# Power_Management.net
KiCad netlist of a schematic drawn in Altium Designer
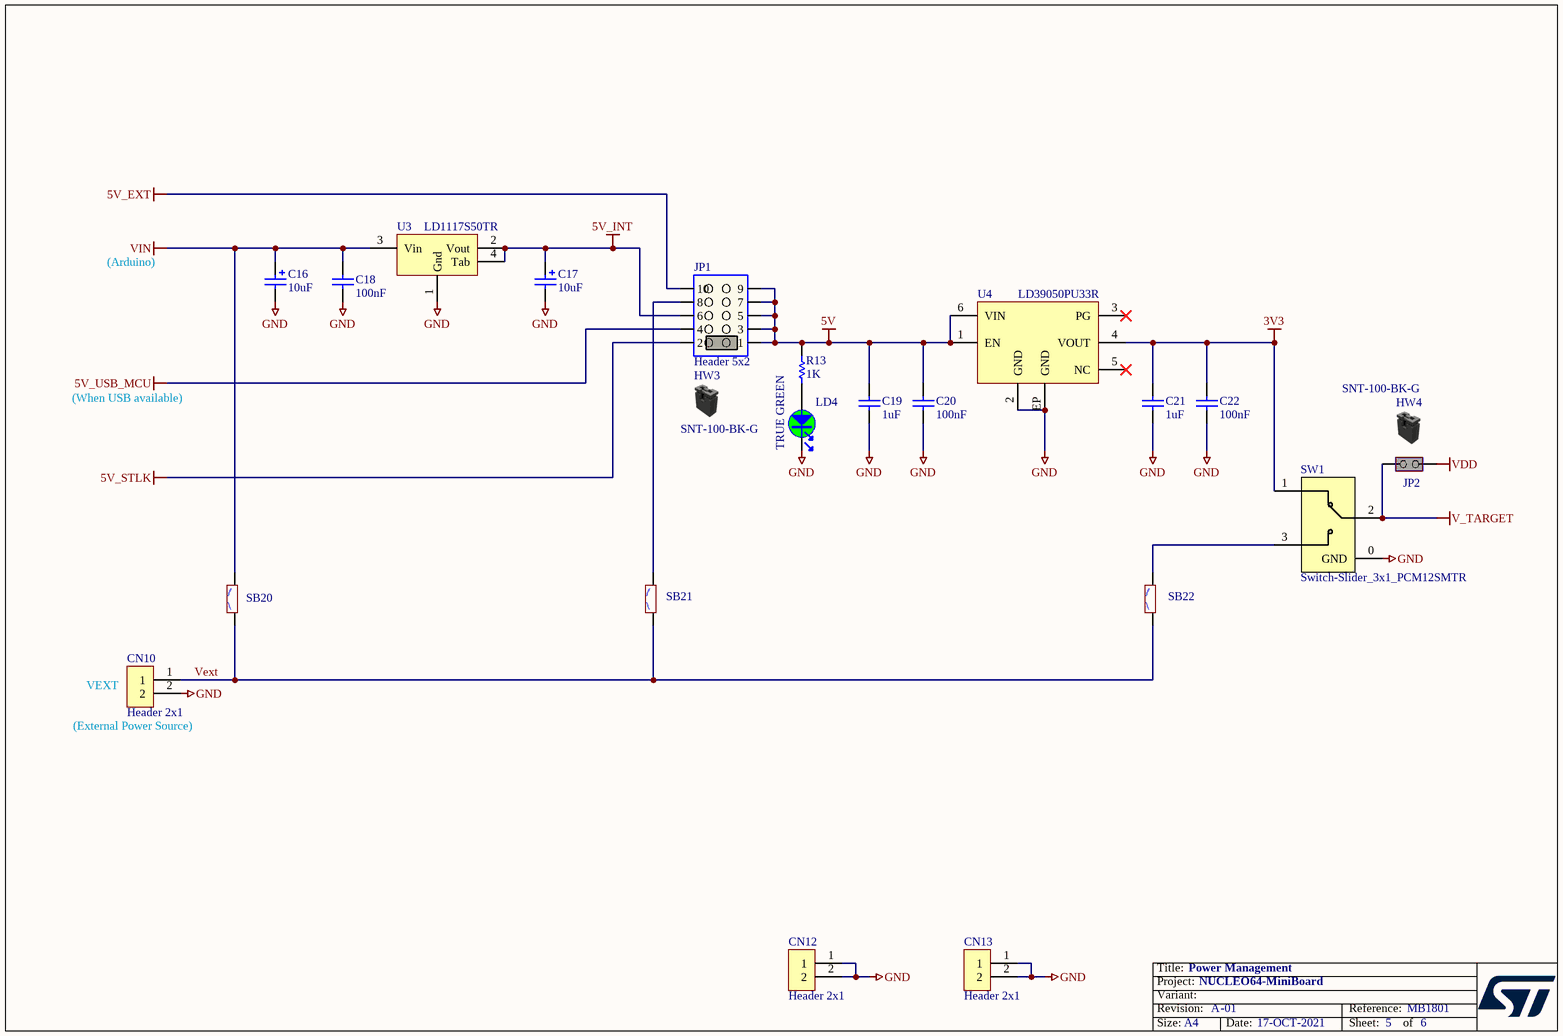
[diagram p0: Power_Management.SchDoc]

(export (version "E")
  (design (tool "Eeschema 10.0.6"))
  (components
    (comp (ref "C16")
      (value "10uF")
      (footprint "CPOL_TAJ-B_1210_H210")
      (description "Capacitor, Tantalum, 10uF, 25V, 2R5, +/-10%, Type_B (3528 metric), T=1.9mm")
      (fields
        (field (name "INTERNAL_PART_NUMBER") "MCD-00324")
        (field (name "MANUFACTURER_PART_NUMBER") "TAJB106K025RNJ")
      )
      (libsource (lib "MCD_PARTS_database") (part "Cap_POL_TANA"))
    )
    (comp (ref "C17")
      (value "10uF")
      (footprint "CPOL_TAJ-B_1210_H210")
      (description "Capacitor, Tantalum, 10uF, 25V, 2R5, +/-10%, Type_B (3528 metric), T=1.9mm")
      (fields
        (field (name "INTERNAL_PART_NUMBER") "MCD-00324")
        (field (name "MANUFACTURER_PART_NUMBER") "TAJB106K025RNJ")
      )
      (libsource (lib "MCD_PARTS_database") (part "Cap_POL_TANA"))
    )
    (comp (ref "C18")
      (value "100nF")
      (footprint "C0402")
      (description "Capacitor, MLCC, 100nF, 25V, X7R, +/-10%, 0402, T=0.5mm")
      (fields (field (name "INTERNAL_PART_NUMBER") "MCD-02355") (field (name "MANUFACTURER") "WALSIN"))
      (libsource (lib "MCD_PARTS_database") (part "Capacitor"))
    )
    (comp (ref "C19")
      (value "1uF")
      (footprint "C0805_H0P85")
      (description "Capacitor, MLCC, 1uF, 16V, X5R, +/-10%, 0805, T=0.85mm")
      (fields
        (field (name "INTERNAL_PART_NUMBER") "MCD-01550")
        (field (name "MANUFACTURER_PART_NUMBER") "CC0805KRX5R7BB105")
      )
      (libsource (lib "MCD_PARTS_database") (part "Capacitor"))
    )
    (comp (ref "C20")
      (value "100nF")
      (footprint "C0402")
      (description "Capacitor, MLCC, 100nF, 25V, X7R, +/-10%, 0402, T=0.5mm")
      (fields (field (name "INTERNAL_PART_NUMBER") "MCD-02355") (field (name "MANUFACTURER") "WALSIN"))
      (libsource (lib "MCD_PARTS_database") (part "Capacitor"))
    )
    (comp (ref "C21")
      (value "1uF")
      (footprint "C0805_H0P85")
      (description "Capacitor, MLCC, 1uF, 16V, X5R, +/-10%, 0805, T=0.85mm")
      (fields
        (field (name "INTERNAL_PART_NUMBER") "MCD-01550")
        (field (name "MANUFACTURER_PART_NUMBER") "CC0805KRX5R7BB105")
      )
      (libsource (lib "MCD_PARTS_database") (part "Capacitor"))
    )
    (comp (ref "C22")
      (value "100nF")
      (footprint "C0402")
      (description "Capacitor, MLCC, 100nF, 25V, X7R, +/-10%, 0402, T=0.5mm")
      (fields (field (name "INTERNAL_PART_NUMBER") "MCD-02355") (field (name "MANUFACTURER") "WALSIN"))
      (libsource (lib "MCD_PARTS_database") (part "Capacitor"))
    )
    (comp (ref "CN10")
      (value "Header 2x1")
      (footprint "CON_SAMTEC_TSW-102-07-G-S")
      (description "Header, 2x1, 2.54mm, VR, TH, T=5.84mm/2.54mm")
      (fields (field (name "INTERNAL_PART_NUMBER") "MCD-00032") (field (name "MANUFACTURER") "SAMTEC"))
      (libsource (lib "MCD_PARTS_database") (part "Header 2x1"))
    )
    (comp (ref "CN12")
      (value "Header 2x1")
      (footprint "CON_SAMTEC_TSW-102-07-G-S")
      (description "Header, 2x1, 2.54mm, VR, TH, T=5.84mm/2.54mm")
      (fields (field (name "INTERNAL_PART_NUMBER") "MCD-00032") (field (name "MANUFACTURER") "SAMTEC"))
      (libsource (lib "MCD_PARTS_database") (part "Header 2x1"))
    )
    (comp (ref "CN13")
      (value "Header 2x1")
      (footprint "CON_SAMTEC_TSW-102-07-G-S")
      (description "Header, 2x1, 2.54mm, VR, TH, T=5.84mm/2.54mm")
      (fields (field (name "INTERNAL_PART_NUMBER") "MCD-00032") (field (name "MANUFACTURER") "SAMTEC"))
      (libsource (lib "MCD_PARTS_database") (part "Header 2x1"))
    )
    (comp (ref "HW3")
      (value "SNT-100-BK-G")
      (description "SHUNT 2.54mm BLACK")
      (fields (field (name "INTERNAL_PART_NUMBER") "MCD-00043") (field (name "MANUFACTURER") "SAMTEC"))
      (libsource (lib "MCD_PARTS_database") (part "Shunt Black 2.54mm"))
    )
    (comp (ref "HW4")
      (value "SNT-100-BK-G")
      (description "SHUNT 2.54mm BLACK")
      (fields (field (name "INTERNAL_PART_NUMBER") "MCD-00043") (field (name "MANUFACTURER") "SAMTEC"))
      (libsource (lib "MCD_PARTS_database") (part "Shunt Black 2.54mm"))
    )
    (comp (ref "JP1")
      (value "Header 5x2")
      (footprint "CON_SAMTEC_TSM-105-01-L-DV")
      (description "Header, 5x2, 2.54mm, VR, SMD, T=5.84mm")
      (fields (field (name "INTERNAL_PART_NUMBER") "MCD-01230") (field (name "BMS_PART_NUMBER") "9183642"))
      (libsource (lib "MCD_PARTS_database") (part "Jumper_Header 5x2 Fitted 1-2"))
    )
    (comp (ref "JP2")
      (value "Jumper_Header 2x1 Fitted")
      (footprint "CON_SAMTEC_TSW-102-07-G-S")
      (description "Header, 2x1, 2.54mm, VR, TH, T=5.84mm/2.54mm")
      (fields
        (field (name "INTERNAL_PART_NUMBER") "MCD-01904")
        (field (name "MANUFACTURER_PART_NUMBER") "TSW-102-07-G-S")
      )
      (libsource (lib "MCD_PARTS_database") (part "Jumper_Header 2x1 Fitted"))
    )
    (comp (ref "LD4")
      (value "TRUE GREEN")
      (footprint "LED_0603_VISHAY_VLMTG1300-GS08_GREEN_1A2K_H0P8")
      (description "LED Green, 0603 SMD, Fw Voltage = 2.8V - 3.6V")
      (fields
        (field (name "INTERNAL_PART_NUMBER") "MCD-00589")
        (field (name "MANUFACTURER_PART_NUMBER") "VLMTG1300-GS08")
      )
      (libsource (lib "MCD_PARTS_database") (part "LED_green"))
    )
    (comp (ref "R13")
      (value "1K")
      (footprint "R0402")
      (description "Resistor, 1K, 0402, +/-1%,1/16W")
      (fields
        (field (name "INTERNAL_PART_NUMBER") "MCD-00061")
        (field (name "MANUFACTURER_PART_NUMBER") "RC0402FR-071KL")
      )
      (libsource (lib "MCD_PARTS_database") (part "Resistor"))
    )
    (comp (ref "SB20")
      (value "SB_OFF")
      (footprint "SOLDER-BRIDGE_R0402-0R")
      (description "Solder Bridge 0402 OFF")
      (fields (field (name "INTERNAL_PART_NUMBER") "MCD-02162") (field (name "MANUFACTURER") "YAGEO"))
      (libsource (lib "MCD_PARTS_database") (part "SB_OFF"))
    )
    (comp (ref "SB21")
      (value "SB_OFF")
      (footprint "SOLDER-BRIDGE_R0402-0R")
      (description "Solder Bridge 0402 OFF")
      (fields (field (name "INTERNAL_PART_NUMBER") "MCD-02162") (field (name "MANUFACTURER") "YAGEO"))
      (libsource (lib "MCD_PARTS_database") (part "SB_OFF"))
    )
    (comp (ref "SB22")
      (value "SB_OFF")
      (footprint "SOLDER-BRIDGE_R0402-0R")
      (description "Solder Bridge 0402 OFF")
      (fields (field (name "INTERNAL_PART_NUMBER") "MCD-02162") (field (name "MANUFACTURER") "YAGEO"))
      (libsource (lib "MCD_PARTS_database") (part "SB_OFF"))
    )
    (comp (ref "SW1")
      (value "Switch-Slider_3x1_PCM12SMTR")
      (footprint "MCD_PARTS:SWI_SPDT-RA_TE-CONNECTIVITY_MLL1200S_1P2T")
      (description "Slide switch, 3x1, 1.5mm, RA, SMT, T=1.65mm")
      (fields (field (name "INTERNAL_PART_NUMBER") "MCD-03571") (field (name "MANUFACTURER") "C&K"))
      (libsource (lib "MCD_PARTS_database") (part "SW_MECA"))
    )
    (comp (ref "U3")
      (value "LD1117S50TR")
      (footprint "REG_SOT223-TAB")
      (description "IC REG LDO 5V 0.8A SOT223")
      (fields
        (field (name "INTERNAL_PART_NUMBER") "MCD-00088")
        (field (name "MANUFACTURER") "STMICROELECTRONICS")
      )
      (libsource (lib "MCD_PARTS_database") (part "LD1117S50TR"))
    )
    (comp (ref "U4")
      (value "LD39050PU33R")
      (footprint "ICC_DFN6-EPAD_3X3_P095")
      (description "Low quiescent current and low noise voltage regulators")
      (fields
        (field (name "INTERNAL_PART_NUMBER") "MCD-00215")
        (field (name "MANUFACTURER") "STMICROELECTRONICS")
      )
      (libsource (lib "MCD_PARTS_database") (part "LD39050PU33R"))
    )
  )
  (nets
    (net (code "1") (name "/Vext") (class "Default")
      (node (ref "CN10") (pin "1") (pinfunction "1_1") (pintype "passive"))
      (node (ref "SB20") (pin "1") (pinfunction "1_1") (pintype "passive"))
      (node (ref "SB21") (pin "1") (pinfunction "1_1") (pintype "passive"))
      (node (ref "SB22") (pin "1") (pinfunction "1_1") (pintype "passive"))
    )
    (net (code "2") (name "3V3") (class "Default")
      (node (ref "C21") (pin "2") (pinfunction "2_2") (pintype "passive"))
      (node (ref "C22") (pin "2") (pinfunction "2_2") (pintype "passive"))
      (node (ref "SW1") (pin "1") (pinfunction "1_1") (pintype "passive"))
      (node (ref "U4") (pin "4") (pinfunction "VOUT_4") (pintype "passive"))
    )
    (net (code "3") (name "5V") (class "Default")
      (node (ref "C19") (pin "2") (pinfunction "2_2") (pintype "passive"))
      (node (ref "C20") (pin "2") (pinfunction "2_2") (pintype "passive"))
      (node (ref "JP1") (pin "1") (pinfunction "1_1") (pintype "passive"))
      (node (ref "JP1") (pin "3") (pinfunction "3_3") (pintype "passive"))
      (node (ref "JP1") (pin "5") (pinfunction "5_5") (pintype "passive"))
      (node (ref "JP1") (pin "7") (pinfunction "7_7") (pintype "passive"))
      (node (ref "JP1") (pin "9") (pinfunction "9_9") (pintype "passive"))
      (node (ref "R13") (pin "2") (pinfunction "2_2") (pintype "passive"))
      (node (ref "U4") (pin "1") (pinfunction "EN_1") (pintype "passive"))
      (node (ref "U4") (pin "6") (pinfunction "VIN_6") (pintype "passive"))
    )
    (net (code "4") (name "5V_EXT") (class "Default")
      (node (ref "JP1") (pin "10") (pinfunction "10_10") (pintype "passive"))
    )
    (net (code "5") (name "5V_INT") (class "Default")
      (node (ref "C17") (pin "1") (pinfunction "1_1") (pintype "passive"))
      (node (ref "JP1") (pin "6") (pinfunction "6_6") (pintype "passive"))
      (node (ref "U3") (pin "2") (pinfunction "Vout_2") (pintype "passive"))
      (node (ref "U3") (pin "4") (pinfunction "Tab_4") (pintype "passive"))
    )
    (net (code "6") (name "5V_STLK") (class "Default")
      (node (ref "JP1") (pin "2") (pinfunction "2_2") (pintype "passive"))
    )
    (net (code "7") (name "5V_USB_MCU") (class "Default")
      (node (ref "JP1") (pin "4") (pinfunction "4_4") (pintype "passive"))
    )
    (net (code "8") (name "GND") (class "Default")
      (node (ref "C16") (pin "2") (pinfunction "2_2") (pintype "passive"))
      (node (ref "C17") (pin "2") (pinfunction "2_2") (pintype "passive"))
      (node (ref "C18") (pin "1") (pinfunction "1_1") (pintype "passive"))
      (node (ref "C19") (pin "1") (pinfunction "1_1") (pintype "passive"))
      (node (ref "C20") (pin "1") (pinfunction "1_1") (pintype "passive"))
      (node (ref "C21") (pin "1") (pinfunction "1_1") (pintype "passive"))
      (node (ref "C22") (pin "1") (pinfunction "1_1") (pintype "passive"))
      (node (ref "CN10") (pin "2") (pinfunction "2_2") (pintype "passive"))
      (node (ref "CN12") (pin "1") (pinfunction "1_1") (pintype "passive"))
      (node (ref "CN12") (pin "2") (pinfunction "2_2") (pintype "passive"))
      (node (ref "CN13") (pin "1") (pinfunction "1_1") (pintype "passive"))
      (node (ref "CN13") (pin "2") (pinfunction "2_2") (pintype "passive"))
      (node (ref "LD4") (pin "2") (pintype "passive"))
      (node (ref "SW1") (pin "0") (pinfunction "GND_0") (pintype "passive"))
      (node (ref "U3") (pin "1") (pinfunction "Gnd_1") (pintype "passive"))
      (node (ref "U4") (pin "2") (pinfunction "GND_2") (pintype "passive"))
      (node (ref "U4") (pin "EP") (pinfunction "GND_EP") (pintype "passive"))
    )
    (net (code "9") (name "Net-(JP1-Pad8)") (class "Default")
      (node (ref "JP1") (pin "8") (pinfunction "8_8") (pintype "passive"))
      (node (ref "SB21") (pin "2") (pinfunction "2_2") (pintype "passive"))
    )
    (net (code "10") (name "Net-(LD4-Pad1)") (class "Default")
      (node (ref "LD4") (pin "1") (pintype "passive"))
      (node (ref "R13") (pin "1") (pinfunction "1_1") (pintype "passive"))
    )
    (net (code "11") (name "Net-(SB22-Pad2)") (class "Default")
      (node (ref "SB22") (pin "2") (pinfunction "2_2") (pintype "passive"))
      (node (ref "SW1") (pin "3") (pinfunction "3_3") (pintype "passive"))
    )
    (net (code "12") (name "VDD") (class "Default")
      (node (ref "JP2") (pin "2") (pinfunction "NO_2") (pintype "passive"))
    )
    (net (code "13") (name "VIN") (class "Default")
      (node (ref "C16") (pin "1") (pinfunction "1_1") (pintype "passive"))
      (node (ref "C18") (pin "2") (pinfunction "2_2") (pintype "passive"))
      (node (ref "SB20") (pin "2") (pinfunction "2_2") (pintype "passive"))
      (node (ref "U3") (pin "3") (pinfunction "Vin_3") (pintype "passive"))
    )
    (net (code "14") (name "V_TARGET") (class "Default")
      (node (ref "JP2") (pin "1") (pinfunction "COMMON_1") (pintype "passive"))
      (node (ref "SW1") (pin "2") (pinfunction "2_2") (pintype "passive"))
    )
    (net (code "15") (name "unconnected-(U4-NC-Pad5)") (class "Default")
      (node (ref "U4") (pin "5") (pinfunction "NC_5") (pintype "passive+no_connect"))
    )
    (net (code "16") (name "unconnected-(U4-PG-Pad3)") (class "Default")
      (node (ref "U4") (pin "3") (pinfunction "PG_3") (pintype "passive+no_connect"))
    )
  )
)
